# a22.net
KiCad netlist of a schematic drawn in EAGLE
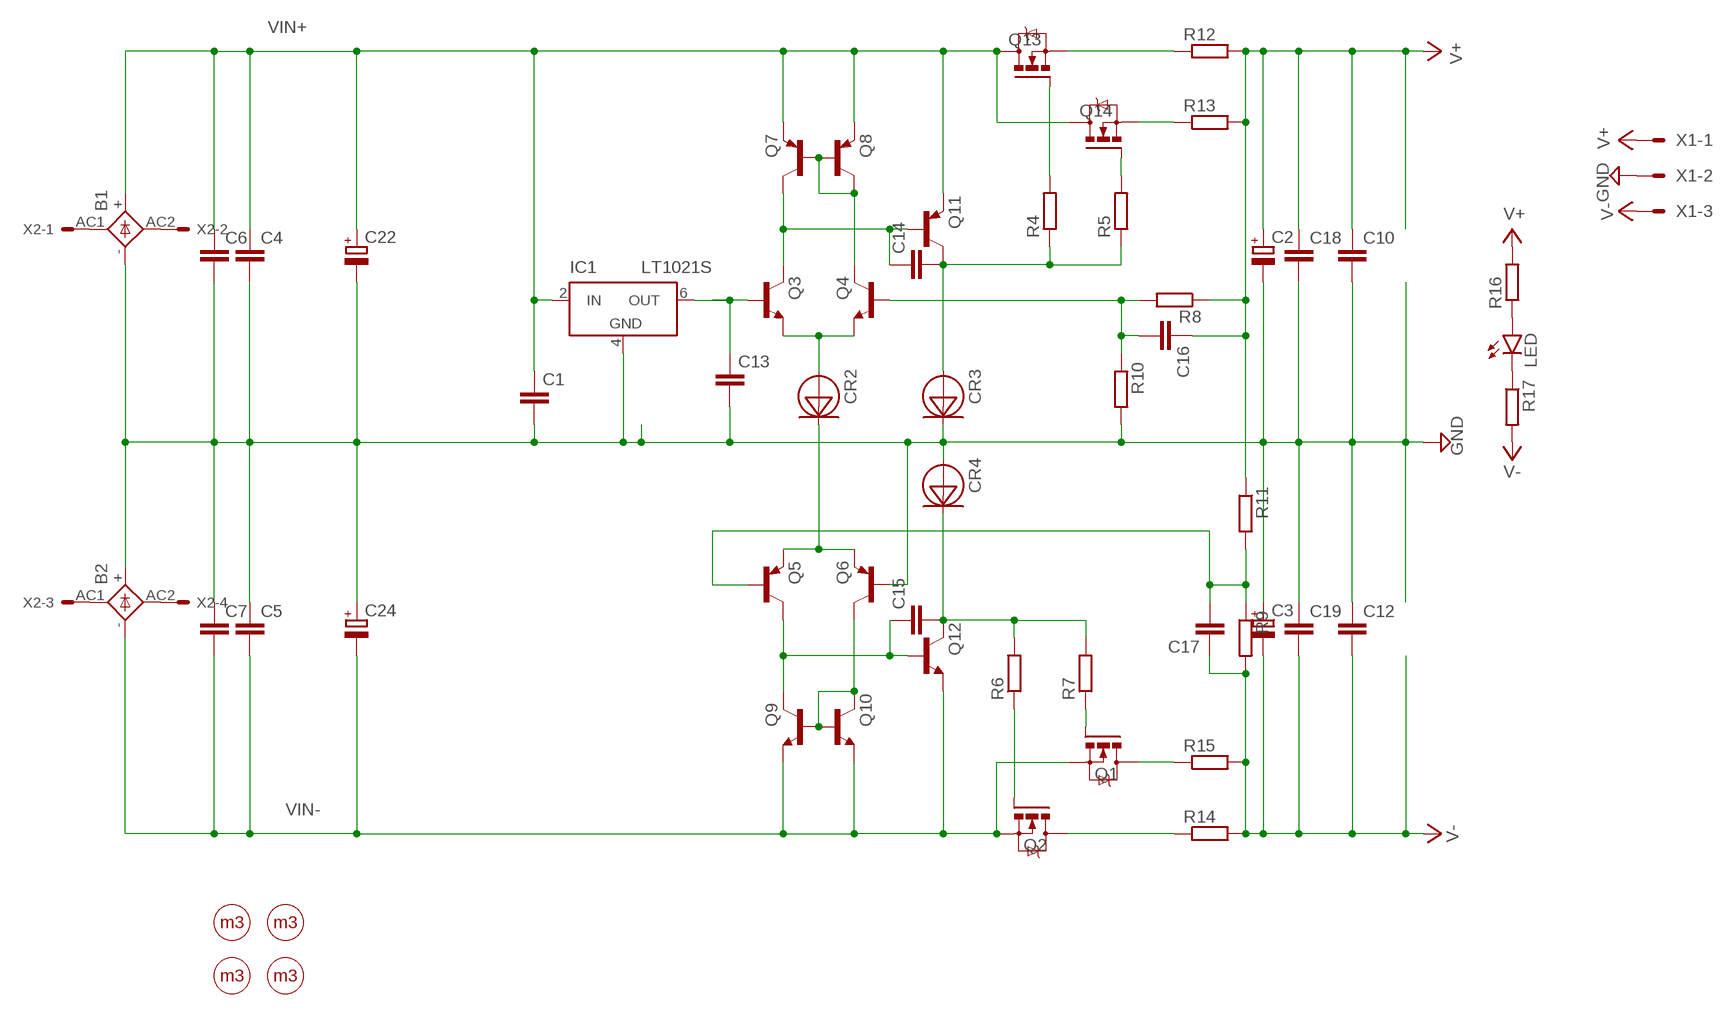
[diagram p0: schematic, sheet 1]

(export (version "E")
  (design (tool "Eeschema 10.0.6"))
  (components
    (comp (ref "B1")
      (value "2KBB-R")
      (footprint "eagle-import:2KBB-R")
      (libsource (lib "eagle-import") (part "2KBB-R"))
    )
    (comp (ref "B2")
      (value "2KBB-R")
      (footprint "eagle-import:2KBB-R")
      (libsource (lib "eagle-import") (part "2KBB-R"))
    )
    (comp (ref "C1")
      (value "C-EUC0805")
      (footprint "eagle-import:C0805")
      (libsource (lib "eagle-import") (part "C-EUC0805"))
    )
    (comp (ref "C2")
      (value "CPOL-EUE5-13")
      (footprint "eagle-import:E5-13")
      (libsource (lib "eagle-import") (part "CPOL-EUE5-13"))
    )
    (comp (ref "C3")
      (value "CPOL-EUE5-13")
      (footprint "eagle-import:E5-13")
      (libsource (lib "eagle-import") (part "CPOL-EUE5-13"))
    )
    (comp (ref "C4")
      (value "C-EU050-050X075")
      (footprint "eagle-import:C050-050X075")
      (libsource (lib "eagle-import") (part "C-EU050-050X075"))
    )
    (comp (ref "C5")
      (value "C-EU050-050X075")
      (footprint "eagle-import:C050-050X075")
      (libsource (lib "eagle-import") (part "C-EU050-050X075"))
    )
    (comp (ref "C6")
      (value "C-EU050-050X075")
      (footprint "eagle-import:C050-050X075")
      (libsource (lib "eagle-import") (part "C-EU050-050X075"))
    )
    (comp (ref "C7")
      (value "C-EU050-050X075")
      (footprint "eagle-import:C050-050X075")
      (libsource (lib "eagle-import") (part "C-EU050-050X075"))
    )
    (comp (ref "C10")
      (value "C-EU050-050X075")
      (footprint "eagle-import:C050-050X075")
      (libsource (lib "eagle-import") (part "C-EU050-050X075"))
    )
    (comp (ref "C12")
      (value "C-EU050-050X075")
      (footprint "eagle-import:C050-050X075")
      (libsource (lib "eagle-import") (part "C-EU050-050X075"))
    )
    (comp (ref "C13")
      (value "C-EUC0805")
      (footprint "eagle-import:C0805")
      (libsource (lib "eagle-import") (part "C-EUC0805"))
    )
    (comp (ref "C14")
      (value "C-EUC0805")
      (footprint "eagle-import:C0805")
      (libsource (lib "eagle-import") (part "C-EUC0805"))
    )
    (comp (ref "C15")
      (value "C-EUC0805")
      (footprint "eagle-import:C0805")
      (libsource (lib "eagle-import") (part "C-EUC0805"))
    )
    (comp (ref "C16")
      (value "C-EUC0805")
      (footprint "eagle-import:C0805")
      (libsource (lib "eagle-import") (part "C-EUC0805"))
    )
    (comp (ref "C17")
      (value "C-EUC0805")
      (footprint "eagle-import:C0805")
      (libsource (lib "eagle-import") (part "C-EUC0805"))
    )
    (comp (ref "C18")
      (value "C-EU050-050X075")
      (footprint "eagle-import:C050-050X075")
      (libsource (lib "eagle-import") (part "C-EU050-050X075"))
    )
    (comp (ref "C19")
      (value "C-EU050-050X075")
      (footprint "eagle-import:C050-050X075")
      (libsource (lib "eagle-import") (part "C-EU050-050X075"))
    )
    (comp (ref "C22")
      (value "CPOL-EUE10-25")
      (footprint "eagle-import:EB25D")
      (libsource (lib "eagle-import") (part "CPOL-EUE10-25"))
    )
    (comp (ref "C24")
      (value "CPOL-EUE10-25")
      (footprint "eagle-import:EB25D")
      (libsource (lib "eagle-import") (part "CPOL-EUE10-25"))
    )
    (comp (ref "CR2")
      (value "1N5283")
      (footprint "eagle-import:SMD")
      (libsource (lib "eagle-import") (part "1N5283"))
    )
    (comp (ref "CR3")
      (value "1N5283")
      (footprint "eagle-import:SMD")
      (libsource (lib "eagle-import") (part "1N5283"))
    )
    (comp (ref "CR4")
      (value "1N5283")
      (footprint "eagle-import:SMD")
      (libsource (lib "eagle-import") (part "1N5283"))
    )
    (comp (ref "IC1")
      (value "LT1021S")
      (footprint "eagle-import:SOIC8")
      (fields (field (name "MPN") "LT1021DCS8-10#PBF"))
      (libsource (lib "eagle-import") (part "LT1021S"))
    )
    (comp (ref "LED")
      (value "LEDVWV1206")
      (footprint "eagle-import:LED_SML1206")
      (libsource (lib "eagle-import") (part "LEDVWV1206"))
    )
    (comp (ref "Q1")
      (value "IRFZ24N")
      (footprint "eagle-import:TRANSISTOR_TO220KG")
      (libsource (lib "eagle-import") (part "IRFZ24N"))
    )
    (comp (ref "Q2")
      (value "IRFZ24N")
      (footprint "eagle-import:TRANSISTOR_TO220KG")
      (libsource (lib "eagle-import") (part "IRFZ24N"))
    )
    (comp (ref "Q3")
      (value "BJT_NPNKSC1845")
      (footprint "eagle-import:TRANSISTOR_TO92-ECB_N")
      (libsource (lib "eagle-import") (part "BJT_NPNKSC1845"))
    )
    (comp (ref "Q4")
      (value "BJT_NPNKSC1845")
      (footprint "eagle-import:TRANSISTOR_TO92-ECB_N")
      (libsource (lib "eagle-import") (part "BJT_NPNKSC1845"))
    )
    (comp (ref "Q5")
      (value "BJT_PNPKSA992")
      (footprint "eagle-import:TRANSISTOR_TO92-ECB_P")
      (libsource (lib "eagle-import") (part "BJT_PNPKSA992"))
    )
    (comp (ref "Q6")
      (value "BJT_PNPKSA992")
      (footprint "eagle-import:TRANSISTOR_TO92-ECB_P")
      (libsource (lib "eagle-import") (part "BJT_PNPKSA992"))
    )
    (comp (ref "Q7")
      (value "BJT_PNPKSA992")
      (footprint "eagle-import:TRANSISTOR_TO92-ECB_P")
      (libsource (lib "eagle-import") (part "BJT_PNPKSA992"))
    )
    (comp (ref "Q8")
      (value "BJT_PNPKSA992")
      (footprint "eagle-import:TRANSISTOR_TO92-ECB_P")
      (libsource (lib "eagle-import") (part "BJT_PNPKSA992"))
    )
    (comp (ref "Q9")
      (value "BJT_NPNKSC1845")
      (footprint "eagle-import:TRANSISTOR_TO92-ECB_N")
      (libsource (lib "eagle-import") (part "BJT_NPNKSC1845"))
    )
    (comp (ref "Q10")
      (value "BJT_NPNKSC1845")
      (footprint "eagle-import:TRANSISTOR_TO92-ECB_N")
      (libsource (lib "eagle-import") (part "BJT_NPNKSC1845"))
    )
    (comp (ref "Q11")
      (value "BJT_PNPKSA992")
      (footprint "eagle-import:TRANSISTOR_TO92-ECB_P")
      (libsource (lib "eagle-import") (part "BJT_PNPKSA992"))
    )
    (comp (ref "Q12")
      (value "BJT_NPNKSC1845")
      (footprint "eagle-import:TRANSISTOR_TO92-ECB_N")
      (libsource (lib "eagle-import") (part "BJT_NPNKSC1845"))
    )
    (comp (ref "Q13")
      (value "IRFZ24N")
      (footprint "eagle-import:TRANSISTOR_TO220KG")
      (libsource (lib "eagle-import") (part "IRFZ24N"))
    )
    (comp (ref "Q14")
      (value "IRFZ24N")
      (footprint "eagle-import:TRANSISTOR_TO220KG")
      (libsource (lib "eagle-import") (part "IRFZ24N"))
    )
    (comp (ref "R4")
      (value "R-EU_MELF0204W")
      (footprint "eagle-import:MINI_MELF-0204W")
      (libsource (lib "eagle-import") (part "R-EU_MELF0204W"))
    )
    (comp (ref "R5")
      (value "R-EU_MELF0204W")
      (footprint "eagle-import:MINI_MELF-0204W")
      (libsource (lib "eagle-import") (part "R-EU_MELF0204W"))
    )
    (comp (ref "R6")
      (value "R-EU_MELF0204W")
      (footprint "eagle-import:MINI_MELF-0204W")
      (libsource (lib "eagle-import") (part "R-EU_MELF0204W"))
    )
    (comp (ref "R7")
      (value "R-EU_MELF0204W")
      (footprint "eagle-import:MINI_MELF-0204W")
      (libsource (lib "eagle-import") (part "R-EU_MELF0204W"))
    )
    (comp (ref "R8")
      (value "R-EU_MELF0204W")
      (footprint "eagle-import:MINI_MELF-0204W")
      (libsource (lib "eagle-import") (part "R-EU_MELF0204W"))
    )
    (comp (ref "R9")
      (value "R-EU_MELF0204W")
      (footprint "eagle-import:MINI_MELF-0204W")
      (libsource (lib "eagle-import") (part "R-EU_MELF0204W"))
    )
    (comp (ref "R10")
      (value "R-EU_MELF0204W")
      (footprint "eagle-import:MINI_MELF-0204W")
      (libsource (lib "eagle-import") (part "R-EU_MELF0204W"))
    )
    (comp (ref "R11")
      (value "R-EU_MELF0204W")
      (footprint "eagle-import:MINI_MELF-0204W")
      (libsource (lib "eagle-import") (part "R-EU_MELF0204W"))
    )
    (comp (ref "R12")
      (value "R-EU_R2512")
      (footprint "eagle-import:R2512")
      (libsource (lib "eagle-import") (part "R-EU_R2512"))
    )
    (comp (ref "R13")
      (value "R-EU_R2512")
      (footprint "eagle-import:R2512")
      (libsource (lib "eagle-import") (part "R-EU_R2512"))
    )
    (comp (ref "R14")
      (value "R-EU_R2512")
      (footprint "eagle-import:R2512")
      (libsource (lib "eagle-import") (part "R-EU_R2512"))
    )
    (comp (ref "R15")
      (value "R-EU_R2512")
      (footprint "eagle-import:R2512")
      (libsource (lib "eagle-import") (part "R-EU_R2512"))
    )
    (comp (ref "R16")
      (value "R-EU_MELF0204W")
      (footprint "eagle-import:MINI_MELF-0204W")
      (libsource (lib "eagle-import") (part "R-EU_MELF0204W"))
    )
    (comp (ref "R17")
      (value "R-EU_MELF0204W")
      (footprint "eagle-import:MINI_MELF-0204W")
      (libsource (lib "eagle-import") (part "R-EU_MELF0204W"))
    )
    (comp (ref "U$1")
      (value "HOLE")
      (footprint "eagle-import:M3_HOLE")
      (libsource (lib "eagle-import") (part "HOLE"))
    )
    (comp (ref "U$2")
      (value "HOLE")
      (footprint "eagle-import:M3_HOLE")
      (libsource (lib "eagle-import") (part "HOLE"))
    )
    (comp (ref "U$3")
      (value "HOLE")
      (footprint "eagle-import:M3_HOLE")
      (libsource (lib "eagle-import") (part "HOLE"))
    )
    (comp (ref "U$4")
      (value "HOLE")
      (footprint "eagle-import:M3_HOLE")
      (libsource (lib "eagle-import") (part "HOLE"))
    )
    (comp (ref "X1")
      (value "KK-156-3")
      (footprint "eagle-import:KK-156-3")
      (fields (field (name "MF") "MOLEX"))
      (libsource (lib "eagle-import") (part "KK-156-3"))
    )
    (comp (ref "X2")
      (value "KK-156-4")
      (footprint "eagle-import:KK-156-4")
      (fields (field (name "MF") "MOLEX"))
      (libsource (lib "eagle-import") (part "KK-156-4"))
    )
  )
  (nets
    (net (code "1") (name "/VIN+") (class "Default")
      (node (ref "B1") (pin "+") (pinfunction "+_+") (pintype "passive"))
      (node (ref "C1") (pin "1") (pinfunction "1_1") (pintype "passive"))
      (node (ref "C22") (pin "+") (pinfunction "+_+") (pintype "passive"))
      (node (ref "C4") (pin "1") (pinfunction "1_1") (pintype "passive"))
      (node (ref "C6") (pin "1") (pinfunction "1_1") (pintype "passive"))
      (node (ref "IC1") (pin "2") (pinfunction "IN_2") (pintype "input"))
      (node (ref "Q11") (pin "E") (pinfunction "E_E") (pintype "passive"))
      (node (ref "Q13") (pin "2") (pinfunction "D_2") (pintype "passive"))
      (node (ref "Q14") (pin "2") (pinfunction "D_2") (pintype "passive"))
      (node (ref "Q7") (pin "E") (pinfunction "E_E") (pintype "passive"))
      (node (ref "Q8") (pin "E") (pinfunction "E_E") (pintype "passive"))
    )
    (net (code "2") (name "/VIN-") (class "Default")
      (node (ref "B2") (pin "-") (pinfunction "-_-") (pintype "passive"))
      (node (ref "C24") (pin "-") (pinfunction "-_-") (pintype "passive"))
      (node (ref "C5") (pin "2") (pinfunction "2_2") (pintype "passive"))
      (node (ref "C7") (pin "2") (pinfunction "2_2") (pintype "passive"))
      (node (ref "Q1") (pin "3") (pinfunction "S_3") (pintype "passive"))
      (node (ref "Q10") (pin "E") (pinfunction "E_E") (pintype "passive"))
      (node (ref "Q12") (pin "E") (pinfunction "E_E") (pintype "passive"))
      (node (ref "Q2") (pin "3") (pinfunction "S_3") (pintype "passive"))
      (node (ref "Q9") (pin "E") (pinfunction "E_E") (pintype "passive"))
    )
    (net (code "3") (name "GND") (class "Default")
      (node (ref "B1") (pin "-") (pinfunction "-_-") (pintype "passive"))
      (node (ref "B2") (pin "+") (pinfunction "+_+") (pintype "passive"))
      (node (ref "C1") (pin "2") (pinfunction "2_2") (pintype "passive"))
      (node (ref "C10") (pin "2") (pinfunction "2_2") (pintype "passive"))
      (node (ref "C12") (pin "1") (pinfunction "1_1") (pintype "passive"))
      (node (ref "C13") (pin "2") (pinfunction "2_2") (pintype "passive"))
      (node (ref "C18") (pin "2") (pinfunction "2_2") (pintype "passive"))
      (node (ref "C19") (pin "1") (pinfunction "1_1") (pintype "passive"))
      (node (ref "C2") (pin "-") (pinfunction "-_-") (pintype "passive"))
      (node (ref "C22") (pin "-") (pinfunction "-_-") (pintype "passive"))
      (node (ref "C24") (pin "+") (pinfunction "+_+") (pintype "passive"))
      (node (ref "C3") (pin "+") (pinfunction "+_+") (pintype "passive"))
      (node (ref "C4") (pin "2") (pinfunction "2_2") (pintype "passive"))
      (node (ref "C5") (pin "1") (pinfunction "1_1") (pintype "passive"))
      (node (ref "C6") (pin "2") (pinfunction "2_2") (pintype "passive"))
      (node (ref "C7") (pin "1") (pinfunction "1_1") (pintype "passive"))
      (node (ref "CR3") (pin "CATHODE") (pinfunction "CATHODE_CATHODE") (pintype "passive"))
      (node (ref "CR4") (pin "ANODE") (pinfunction "ANODE_ANODE") (pintype "passive"))
      (node (ref "IC1") (pin "4") (pinfunction "GND_4") (pintype "power_in"))
      (node (ref "Q6") (pin "B") (pinfunction "B_B") (pintype "passive"))
      (node (ref "R10") (pin "2") (pinfunction "2_2") (pintype "passive"))
      (node (ref "X1") (pin "2") (pinfunction "S_2") (pintype "passive"))
    )
    (net (code "4") (name "Net-(C14-Pad1)") (class "Default")
      (node (ref "C14") (pin "1") (pinfunction "1_1") (pintype "passive"))
      (node (ref "Q11") (pin "B") (pinfunction "B_B") (pintype "passive"))
      (node (ref "Q3") (pin "C") (pinfunction "C_C") (pintype "passive"))
      (node (ref "Q7") (pin "C") (pinfunction "C_C") (pintype "passive"))
    )
    (net (code "5") (name "Net-(C14-Pad2)") (class "Default")
      (node (ref "C14") (pin "2") (pinfunction "2_2") (pintype "passive"))
      (node (ref "CR3") (pin "ANODE") (pinfunction "ANODE_ANODE") (pintype "passive"))
      (node (ref "Q11") (pin "C") (pinfunction "C_C") (pintype "passive"))
      (node (ref "R4") (pin "1") (pinfunction "1_1") (pintype "passive"))
      (node (ref "R5") (pin "1") (pinfunction "1_1") (pintype "passive"))
    )
    (net (code "6") (name "Net-(C15-Pad1)") (class "Default")
      (node (ref "C15") (pin "1") (pinfunction "1_1") (pintype "passive"))
      (node (ref "Q12") (pin "B") (pinfunction "B_B") (pintype "passive"))
      (node (ref "Q5") (pin "C") (pinfunction "C_C") (pintype "passive"))
      (node (ref "Q9") (pin "C") (pinfunction "C_C") (pintype "passive"))
    )
    (net (code "7") (name "Net-(C15-Pad2)") (class "Default")
      (node (ref "C15") (pin "2") (pinfunction "2_2") (pintype "passive"))
      (node (ref "CR4") (pin "CATHODE") (pinfunction "CATHODE_CATHODE") (pintype "passive"))
      (node (ref "Q12") (pin "C") (pinfunction "C_C") (pintype "passive"))
      (node (ref "R6") (pin "2") (pinfunction "2_2") (pintype "passive"))
      (node (ref "R7") (pin "2") (pinfunction "2_2") (pintype "passive"))
    )
    (net (code "8") (name "Net-(C16-Pad2)") (class "Default")
      (node (ref "C16") (pin "2") (pinfunction "2_2") (pintype "passive"))
      (node (ref "Q4") (pin "B") (pinfunction "B_B") (pintype "passive"))
      (node (ref "R10") (pin "1") (pinfunction "1_1") (pintype "passive"))
      (node (ref "R8") (pin "2") (pinfunction "2_2") (pintype "passive"))
    )
    (net (code "9") (name "Net-(C17-Pad2)") (class "Default")
      (node (ref "C17") (pin "2") (pinfunction "2_2") (pintype "passive"))
      (node (ref "Q5") (pin "B") (pinfunction "B_B") (pintype "passive"))
      (node (ref "R11") (pin "2") (pinfunction "2_2") (pintype "passive"))
      (node (ref "R9") (pin "1") (pinfunction "1_1") (pintype "passive"))
    )
    (net (code "10") (name "Net-(CR2-PadANODE)") (class "Default")
      (node (ref "CR2") (pin "ANODE") (pinfunction "ANODE_ANODE") (pintype "passive"))
      (node (ref "Q3") (pin "E") (pinfunction "E_E") (pintype "passive"))
      (node (ref "Q4") (pin "E") (pinfunction "E_E") (pintype "passive"))
    )
    (net (code "11") (name "Net-(CR2-PadCATHODE)") (class "Default")
      (node (ref "CR2") (pin "CATHODE") (pinfunction "CATHODE_CATHODE") (pintype "passive"))
      (node (ref "Q5") (pin "E") (pinfunction "E_E") (pintype "passive"))
      (node (ref "Q6") (pin "E") (pinfunction "E_E") (pintype "passive"))
    )
    (net (code "12") (name "Net-(IC1-OUT)") (class "Default")
      (node (ref "C13") (pin "1") (pinfunction "1_1") (pintype "passive"))
      (node (ref "IC1") (pin "6") (pinfunction "OUT_6") (pintype "output"))
      (node (ref "Q3") (pin "B") (pinfunction "B_B") (pintype "passive"))
    )
    (net (code "13") (name "Net-(LED-PadA)") (class "Default")
      (node (ref "LED") (pin "A") (pinfunction "A_A") (pintype "passive"))
      (node (ref "R16") (pin "1") (pinfunction "1_1") (pintype "passive"))
    )
    (net (code "14") (name "Net-(LED-PadC)") (class "Default")
      (node (ref "LED") (pin "C") (pinfunction "C_C") (pintype "passive"))
      (node (ref "R17") (pin "1") (pinfunction "1_1") (pintype "passive"))
    )
    (net (code "15") (name "Net-(Q1-D)") (class "Default")
      (node (ref "Q1") (pin "2") (pinfunction "D_2") (pintype "passive"))
      (node (ref "R15") (pin "1") (pinfunction "1_1") (pintype "passive"))
    )
    (net (code "16") (name "Net-(Q1-G)") (class "Default")
      (node (ref "Q1") (pin "1") (pinfunction "G_1") (pintype "passive"))
      (node (ref "R7") (pin "1") (pinfunction "1_1") (pintype "passive"))
    )
    (net (code "17") (name "Net-(Q2-D)") (class "Default")
      (node (ref "Q2") (pin "2") (pinfunction "D_2") (pintype "passive"))
      (node (ref "R14") (pin "1") (pinfunction "1_1") (pintype "passive"))
    )
    (net (code "18") (name "Net-(Q2-G)") (class "Default")
      (node (ref "Q2") (pin "1") (pinfunction "G_1") (pintype "passive"))
      (node (ref "R6") (pin "1") (pinfunction "1_1") (pintype "passive"))
    )
    (net (code "19") (name "Net-(Q4-PadC)") (class "Default")
      (node (ref "Q4") (pin "C") (pinfunction "C_C") (pintype "passive"))
      (node (ref "Q7") (pin "B") (pinfunction "B_B") (pintype "passive"))
      (node (ref "Q8") (pin "B") (pinfunction "B_B") (pintype "passive"))
      (node (ref "Q8") (pin "C") (pinfunction "C_C") (pintype "passive"))
    )
    (net (code "20") (name "Net-(Q10-PadB)") (class "Default")
      (node (ref "Q10") (pin "B") (pinfunction "B_B") (pintype "passive"))
      (node (ref "Q10") (pin "C") (pinfunction "C_C") (pintype "passive"))
      (node (ref "Q6") (pin "C") (pinfunction "C_C") (pintype "passive"))
      (node (ref "Q9") (pin "B") (pinfunction "B_B") (pintype "passive"))
    )
    (net (code "21") (name "Net-(Q13-G)") (class "Default")
      (node (ref "Q13") (pin "1") (pinfunction "G_1") (pintype "passive"))
      (node (ref "R4") (pin "2") (pinfunction "2_2") (pintype "passive"))
    )
    (net (code "22") (name "Net-(Q13-S)") (class "Default")
      (node (ref "Q13") (pin "3") (pinfunction "S_3") (pintype "passive"))
      (node (ref "R12") (pin "1") (pinfunction "1_1") (pintype "passive"))
    )
    (net (code "23") (name "Net-(Q14-G)") (class "Default")
      (node (ref "Q14") (pin "1") (pinfunction "G_1") (pintype "passive"))
      (node (ref "R5") (pin "2") (pinfunction "2_2") (pintype "passive"))
    )
    (net (code "24") (name "Net-(Q14-S)") (class "Default")
      (node (ref "Q14") (pin "3") (pinfunction "S_3") (pintype "passive"))
      (node (ref "R13") (pin "1") (pinfunction "1_1") (pintype "passive"))
    )
    (net (code "25") (name "Net-(X2A-S)") (class "Default")
      (node (ref "B1") (pin "AC1") (pinfunction "AC1_AC1") (pintype "passive"))
      (node (ref "X2") (pin "1") (pinfunction "S_1") (pintype "passive"))
    )
    (net (code "26") (name "Net-(X2B-S)") (class "Default")
      (node (ref "B1") (pin "AC2") (pinfunction "AC2_AC2") (pintype "passive"))
      (node (ref "X2") (pin "2") (pinfunction "S_2") (pintype "passive"))
    )
    (net (code "27") (name "Net-(X2C-S)") (class "Default")
      (node (ref "B2") (pin "AC1") (pinfunction "AC1_AC1") (pintype "passive"))
      (node (ref "X2") (pin "3") (pinfunction "S_3") (pintype "passive"))
    )
    (net (code "28") (name "Net-(X2D-S)") (class "Default")
      (node (ref "B2") (pin "AC2") (pinfunction "AC2_AC2") (pintype "passive"))
      (node (ref "X2") (pin "4") (pinfunction "S_4") (pintype "passive"))
    )
    (net (code "29") (name "V+") (class "Default")
      (node (ref "C10") (pin "1") (pinfunction "1_1") (pintype "passive"))
      (node (ref "C16") (pin "1") (pinfunction "1_1") (pintype "passive"))
      (node (ref "C18") (pin "1") (pinfunction "1_1") (pintype "passive"))
      (node (ref "C2") (pin "+") (pinfunction "+_+") (pintype "passive"))
      (node (ref "R11") (pin "1") (pinfunction "1_1") (pintype "passive"))
      (node (ref "R12") (pin "2") (pinfunction "2_2") (pintype "passive"))
      (node (ref "R13") (pin "2") (pinfunction "2_2") (pintype "passive"))
      (node (ref "R16") (pin "2") (pinfunction "2_2") (pintype "passive"))
      (node (ref "R8") (pin "1") (pinfunction "1_1") (pintype "passive"))
      (node (ref "X1") (pin "1") (pinfunction "S_1") (pintype "passive"))
    )
    (net (code "30") (name "V-") (class "Default")
      (node (ref "C12") (pin "2") (pinfunction "2_2") (pintype "passive"))
      (node (ref "C17") (pin "1") (pinfunction "1_1") (pintype "passive"))
      (node (ref "C19") (pin "2") (pinfunction "2_2") (pintype "passive"))
      (node (ref "C3") (pin "-") (pinfunction "-_-") (pintype "passive"))
      (node (ref "R14") (pin "2") (pinfunction "2_2") (pintype "passive"))
      (node (ref "R15") (pin "2") (pinfunction "2_2") (pintype "passive"))
      (node (ref "R17") (pin "2") (pinfunction "2_2") (pintype "passive"))
      (node (ref "R9") (pin "2") (pinfunction "2_2") (pintype "passive"))
      (node (ref "X1") (pin "3") (pinfunction "S_3") (pintype "passive"))
    )
  )
)
